# Parameter-Board-8.net
KiCad netlist of a schematic drawn in EAGLE
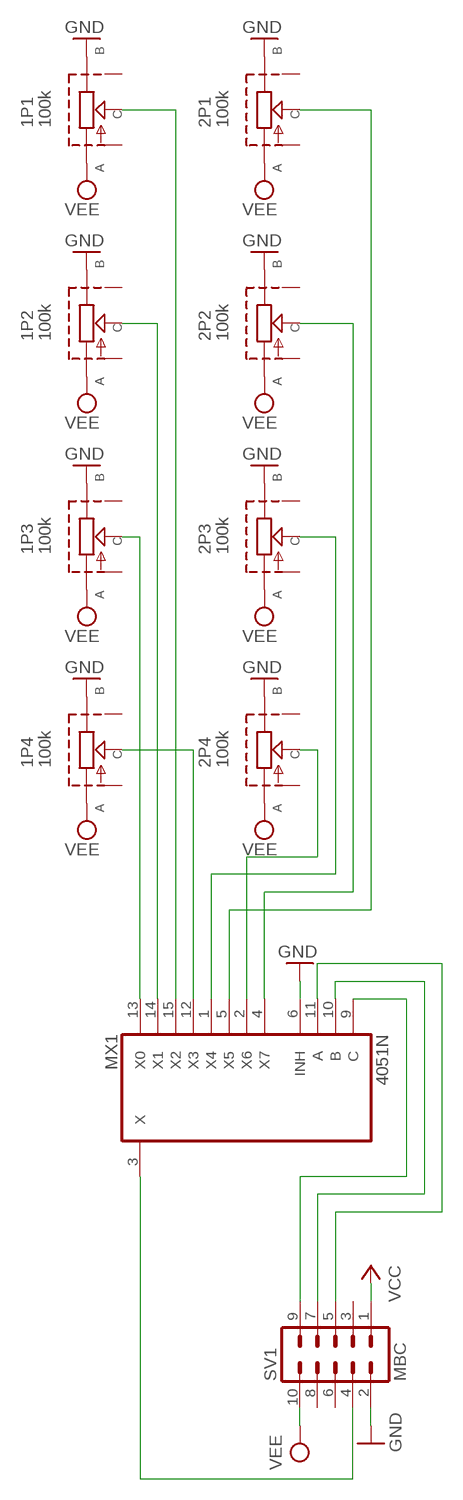
[diagram p0: schematic, sheet 1]

(export (version "E")
  (design (tool "Eeschema 10.0.6"))
  (components
    (comp (ref "1P1")
      (value "100k")
      (footprint "eagle-import:RK09K113")
      (libsource (lib "eagle-import") (part "RK09K113"))
    )
    (comp (ref "1P2")
      (value "100k")
      (footprint "eagle-import:RK09K113")
      (libsource (lib "eagle-import") (part "RK09K113"))
    )
    (comp (ref "1P3")
      (value "100k")
      (footprint "eagle-import:RK09K113")
      (libsource (lib "eagle-import") (part "RK09K113"))
    )
    (comp (ref "1P4")
      (value "100k")
      (footprint "eagle-import:RK09K113")
      (libsource (lib "eagle-import") (part "RK09K113"))
    )
    (comp (ref "2P1")
      (value "100k")
      (footprint "eagle-import:RK09K113")
      (libsource (lib "eagle-import") (part "RK09K113"))
    )
    (comp (ref "2P2")
      (value "100k")
      (footprint "eagle-import:RK09K113")
      (libsource (lib "eagle-import") (part "RK09K113"))
    )
    (comp (ref "2P3")
      (value "100k")
      (footprint "eagle-import:RK09K113")
      (libsource (lib "eagle-import") (part "RK09K113"))
    )
    (comp (ref "2P4")
      (value "100k")
      (footprint "eagle-import:RK09K113")
      (libsource (lib "eagle-import") (part "RK09K113"))
    )
    (comp (ref "MX1")
      (value "4051N")
      (footprint "eagle-import:DIL16")
      (libsource (lib "eagle-import") (part "4051N"))
    )
    (comp (ref "SV1")
      (value "MBC")
      (footprint "eagle-import:ML10")
      (libsource (lib "eagle-import") (part "ML10"))
    )
  )
  (nets
    (net (code "1") (name "GND") (class "Default")
      (node (ref "1P1") (pin "B") (pinfunction "B_B") (pintype "passive"))
      (node (ref "1P2") (pin "B") (pinfunction "B_B") (pintype "passive"))
      (node (ref "1P3") (pin "B") (pinfunction "B_B") (pintype "passive"))
      (node (ref "1P4") (pin "B") (pinfunction "B_B") (pintype "passive"))
      (node (ref "2P1") (pin "B") (pinfunction "B_B") (pintype "passive"))
      (node (ref "2P2") (pin "B") (pinfunction "B_B") (pintype "passive"))
      (node (ref "2P3") (pin "B") (pinfunction "B_B") (pintype "passive"))
      (node (ref "2P4") (pin "B") (pinfunction "B_B") (pintype "passive"))
      (node (ref "MX1") (pin "6") (pinfunction "INH_6") (pintype "input"))
      (node (ref "SV1") (pin "2") (pinfunction "2_2") (pintype "passive"))
    )
    (net (code "2") (name "Net-(MX1A-A)") (class "Default")
      (node (ref "MX1") (pin "11") (pinfunction "A_11") (pintype "input"))
      (node (ref "SV1") (pin "5") (pinfunction "5_5") (pintype "passive"))
    )
    (net (code "3") (name "Net-(MX1A-B)") (class "Default")
      (node (ref "MX1") (pin "10") (pinfunction "B_10") (pintype "input"))
      (node (ref "SV1") (pin "7") (pinfunction "7_7") (pintype "passive"))
    )
    (net (code "4") (name "Net-(MX1A-C)") (class "Default")
      (node (ref "MX1") (pin "9") (pinfunction "C_9") (pintype "input"))
      (node (ref "SV1") (pin "9") (pinfunction "9_9") (pintype "passive"))
    )
    (net (code "5") (name "Net-(MX1A-X)") (class "Default")
      (node (ref "MX1") (pin "3") (pinfunction "X_3") (pintype "bidirectional"))
      (node (ref "SV1") (pin "4") (pinfunction "4_4") (pintype "passive"))
    )
    (net (code "6") (name "Net-(MX1A-X0)") (class "Default")
      (node (ref "1P3") (pin "C") (pinfunction "C_C") (pintype "passive"))
      (node (ref "MX1") (pin "13") (pinfunction "X0_13") (pintype "bidirectional"))
    )
    (net (code "7") (name "Net-(MX1A-X1)") (class "Default")
      (node (ref "1P2") (pin "C") (pinfunction "C_C") (pintype "passive"))
      (node (ref "MX1") (pin "14") (pinfunction "X1_14") (pintype "bidirectional"))
    )
    (net (code "8") (name "Net-(MX1A-X2)") (class "Default")
      (node (ref "1P1") (pin "C") (pinfunction "C_C") (pintype "passive"))
      (node (ref "MX1") (pin "15") (pinfunction "X2_15") (pintype "bidirectional"))
    )
    (net (code "9") (name "Net-(MX1A-X3)") (class "Default")
      (node (ref "1P4") (pin "C") (pinfunction "C_C") (pintype "passive"))
      (node (ref "MX1") (pin "12") (pinfunction "X3_12") (pintype "bidirectional"))
    )
    (net (code "10") (name "Net-(MX1A-X4)") (class "Default")
      (node (ref "2P3") (pin "C") (pinfunction "C_C") (pintype "passive"))
      (node (ref "MX1") (pin "1") (pinfunction "X4_1") (pintype "bidirectional"))
    )
    (net (code "11") (name "Net-(MX1A-X5)") (class "Default")
      (node (ref "2P1") (pin "C") (pinfunction "C_C") (pintype "passive"))
      (node (ref "MX1") (pin "5") (pinfunction "X5_5") (pintype "bidirectional"))
    )
    (net (code "12") (name "Net-(MX1A-X6)") (class "Default")
      (node (ref "2P4") (pin "C") (pinfunction "C_C") (pintype "passive"))
      (node (ref "MX1") (pin "2") (pinfunction "X6_2") (pintype "bidirectional"))
    )
    (net (code "13") (name "Net-(MX1A-X7)") (class "Default")
      (node (ref "2P2") (pin "C") (pinfunction "C_C") (pintype "passive"))
      (node (ref "MX1") (pin "4") (pinfunction "X7_4") (pintype "bidirectional"))
    )
    (net (code "14") (name "VCC") (class "Default")
      (node (ref "SV1") (pin "1") (pinfunction "1_1") (pintype "passive"))
    )
    (net (code "15") (name "VEE") (class "Default")
      (node (ref "1P1") (pin "A") (pinfunction "A_A") (pintype "passive"))
      (node (ref "1P2") (pin "A") (pinfunction "A_A") (pintype "passive"))
      (node (ref "1P3") (pin "A") (pinfunction "A_A") (pintype "passive"))
      (node (ref "1P4") (pin "A") (pinfunction "A_A") (pintype "passive"))
      (node (ref "2P1") (pin "A") (pinfunction "A_A") (pintype "passive"))
      (node (ref "2P2") (pin "A") (pinfunction "A_A") (pintype "passive"))
      (node (ref "2P3") (pin "A") (pinfunction "A_A") (pintype "passive"))
      (node (ref "2P4") (pin "A") (pinfunction "A_A") (pintype "passive"))
      (node (ref "SV1") (pin "10") (pinfunction "10_10") (pintype "passive"))
    )
    (net (code "16") (name "unconnected-(1P1-PadCASE1)") (class "Default")
      (node (ref "1P1") (pin "CASE1") (pinfunction "CASE1_CASE1") (pintype "passive"))
    )
    (net (code "17") (name "unconnected-(1P1-PadCASE2)") (class "Default")
      (node (ref "1P1") (pin "CASE2") (pinfunction "CASE2_CASE2") (pintype "passive"))
    )
    (net (code "18") (name "unconnected-(1P2-PadCASE1)") (class "Default")
      (node (ref "1P2") (pin "CASE1") (pinfunction "CASE1_CASE1") (pintype "passive"))
    )
    (net (code "19") (name "unconnected-(1P2-PadCASE2)") (class "Default")
      (node (ref "1P2") (pin "CASE2") (pinfunction "CASE2_CASE2") (pintype "passive"))
    )
    (net (code "20") (name "unconnected-(1P3-PadCASE1)") (class "Default")
      (node (ref "1P3") (pin "CASE1") (pinfunction "CASE1_CASE1") (pintype "passive"))
    )
    (net (code "21") (name "unconnected-(1P3-PadCASE2)") (class "Default")
      (node (ref "1P3") (pin "CASE2") (pinfunction "CASE2_CASE2") (pintype "passive"))
    )
    (net (code "22") (name "unconnected-(1P4-PadCASE1)") (class "Default")
      (node (ref "1P4") (pin "CASE1") (pinfunction "CASE1_CASE1") (pintype "passive"))
    )
    (net (code "23") (name "unconnected-(1P4-PadCASE2)") (class "Default")
      (node (ref "1P4") (pin "CASE2") (pinfunction "CASE2_CASE2") (pintype "passive"))
    )
    (net (code "24") (name "unconnected-(2P1-PadCASE1)") (class "Default")
      (node (ref "2P1") (pin "CASE1") (pinfunction "CASE1_CASE1") (pintype "passive"))
    )
    (net (code "25") (name "unconnected-(2P1-PadCASE2)") (class "Default")
      (node (ref "2P1") (pin "CASE2") (pinfunction "CASE2_CASE2") (pintype "passive"))
    )
    (net (code "26") (name "unconnected-(2P2-PadCASE1)") (class "Default")
      (node (ref "2P2") (pin "CASE1") (pinfunction "CASE1_CASE1") (pintype "passive"))
    )
    (net (code "27") (name "unconnected-(2P2-PadCASE2)") (class "Default")
      (node (ref "2P2") (pin "CASE2") (pinfunction "CASE2_CASE2") (pintype "passive"))
    )
    (net (code "28") (name "unconnected-(2P3-PadCASE1)") (class "Default")
      (node (ref "2P3") (pin "CASE1") (pinfunction "CASE1_CASE1") (pintype "passive"))
    )
    (net (code "29") (name "unconnected-(2P3-PadCASE2)") (class "Default")
      (node (ref "2P3") (pin "CASE2") (pinfunction "CASE2_CASE2") (pintype "passive"))
    )
    (net (code "30") (name "unconnected-(2P4-PadCASE1)") (class "Default")
      (node (ref "2P4") (pin "CASE1") (pinfunction "CASE1_CASE1") (pintype "passive"))
    )
    (net (code "31") (name "unconnected-(2P4-PadCASE2)") (class "Default")
      (node (ref "2P4") (pin "CASE2") (pinfunction "CASE2_CASE2") (pintype "passive"))
    )
    (net (code "32") (name "unconnected-(SV1-Pad3)") (class "Default")
      (node (ref "SV1") (pin "3") (pinfunction "3_3") (pintype "passive"))
    )
    (net (code "33") (name "unconnected-(SV1-Pad6)") (class "Default")
      (node (ref "SV1") (pin "6") (pinfunction "6_6") (pintype "passive"))
    )
    (net (code "34") (name "unconnected-(SV1-Pad8)") (class "Default")
      (node (ref "SV1") (pin "8") (pinfunction "8_8") (pintype "passive"))
    )
  )
)
